# controlo_rev2.net
KiCad netlist of a schematic drawn in Altium Designer
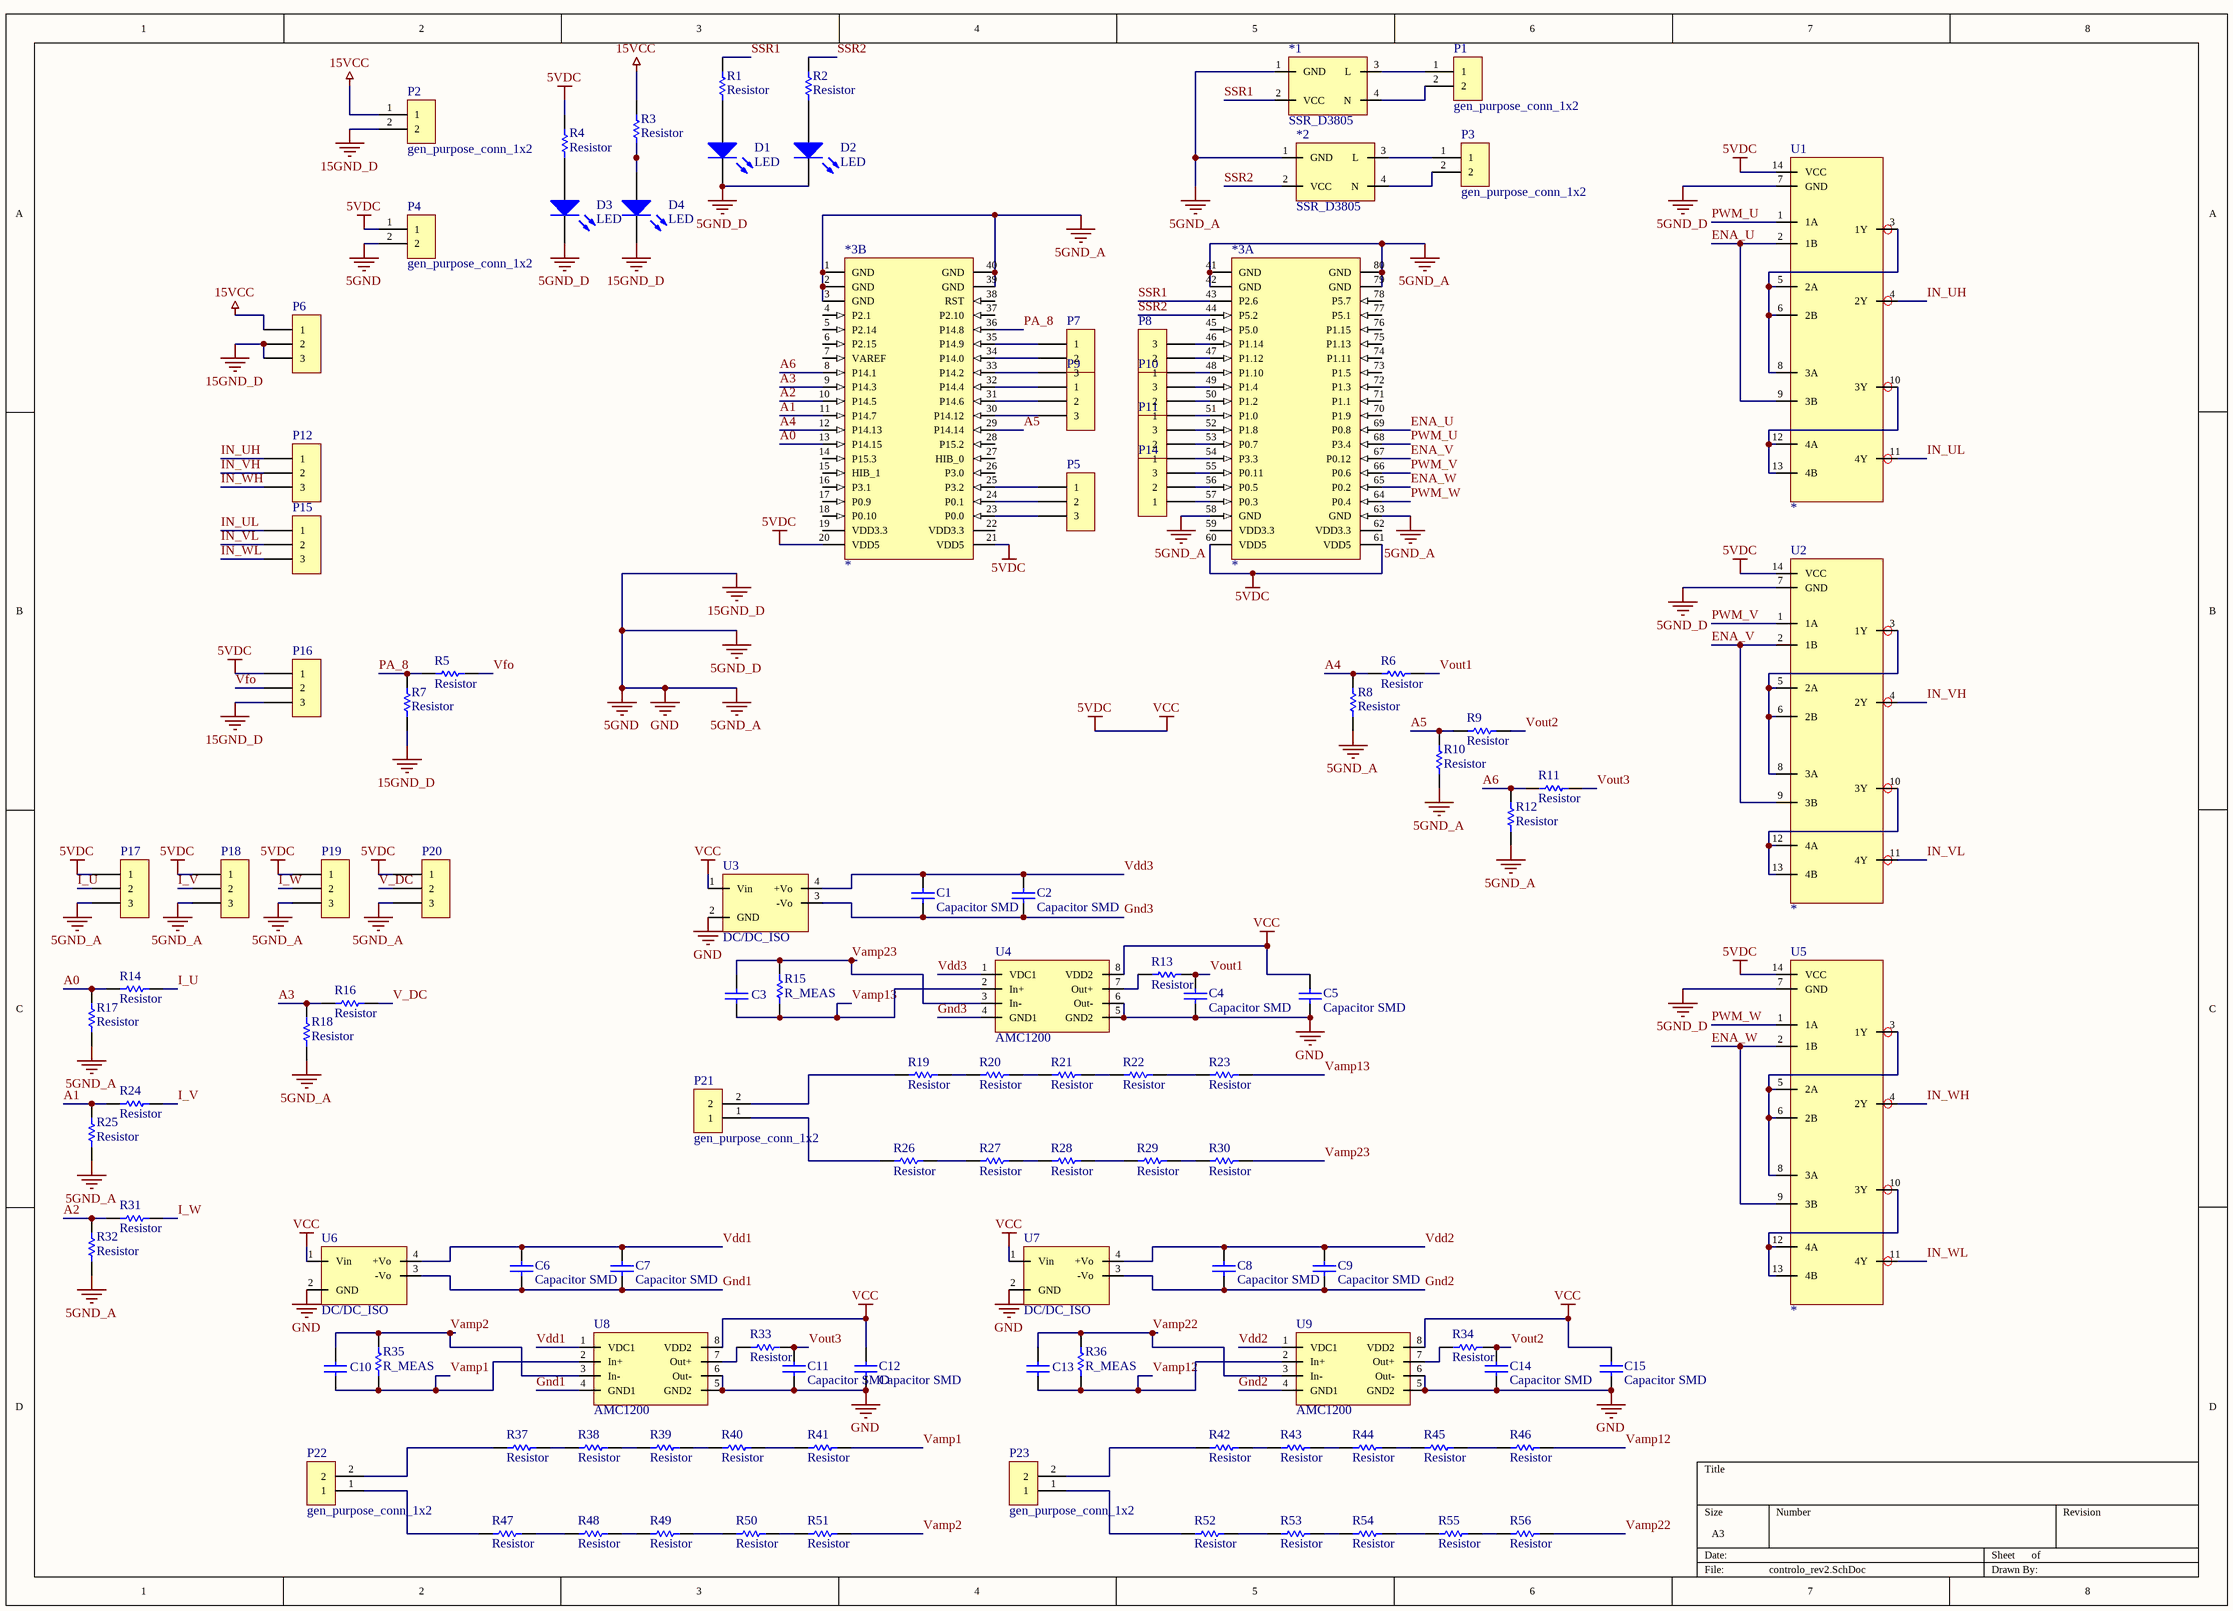
[diagram p0: controlo_rev2.SchDoc]

(export (version "E")
  (design (tool "Eeschema 10.0.6"))
  (components
    (comp (ref "*1")
      (value "SSR_D3805")
      (footprint "SSR_D3805HK")
      (libsource (lib "vmorais_libraries") (part "SSR_D3805"))
    )
    (comp (ref "*2")
      (value "SSR_D3805")
      (footprint "SSR_D3805HK")
      (libsource (lib "vmorais_libraries") (part "SSR_D3805"))
    )
    (comp (ref "*3") (value "*") (footprint "XMC4500") (libsource (lib "vmorais_libraries") (part "XMC4500")))
    (comp (ref "C1")
      (value "Capacitor SMD")
      (footprint "CAPC_0805")
      (description "10uF")
      (libsource (lib "vi_measurement") (part "Capacitor SMD"))
    )
    (comp (ref "C2")
      (value "Capacitor SMD")
      (footprint "CAPC_0805")
      (description "10uF")
      (libsource (lib "vi_measurement") (part "Capacitor SMD"))
    )
    (comp (ref "C3")
      (value "Capacitor SMD")
      (footprint "CAPC_0805")
      (description "1uF")
      (libsource (lib "vi_measurement") (part "Capacitor SMD"))
    )
    (comp (ref "C4")
      (value "Capacitor SMD")
      (footprint "CAPC_0805")
      (description "1uF")
      (libsource (lib "vi_measurement") (part "Capacitor SMD"))
    )
    (comp (ref "C5")
      (value "Capacitor SMD")
      (footprint "CAPC_0805")
      (description "10uF")
      (libsource (lib "vi_measurement") (part "Capacitor SMD"))
    )
    (comp (ref "C6")
      (value "Capacitor SMD")
      (footprint "CAPC_0805")
      (description "10uF")
      (libsource (lib "vi_measurement") (part "Capacitor SMD"))
    )
    (comp (ref "C7")
      (value "Capacitor SMD")
      (footprint "CAPC_0805")
      (description "10uF")
      (libsource (lib "vi_measurement") (part "Capacitor SMD"))
    )
    (comp (ref "C8")
      (value "Capacitor SMD")
      (footprint "CAPC_0805")
      (description "10uF")
      (libsource (lib "vi_measurement") (part "Capacitor SMD"))
    )
    (comp (ref "C9")
      (value "Capacitor SMD")
      (footprint "CAPC_0805")
      (description "10uF")
      (libsource (lib "vi_measurement") (part "Capacitor SMD"))
    )
    (comp (ref "C10")
      (value "Capacitor SMD")
      (footprint "CAPC_0805")
      (description "1uF")
      (libsource (lib "vi_measurement") (part "Capacitor SMD"))
    )
    (comp (ref "C11")
      (value "Capacitor SMD")
      (footprint "CAPC_0805")
      (description "1uF")
      (libsource (lib "vi_measurement") (part "Capacitor SMD"))
    )
    (comp (ref "C12")
      (value "Capacitor SMD")
      (footprint "CAPC_0805")
      (description "10uF")
      (libsource (lib "vi_measurement") (part "Capacitor SMD"))
    )
    (comp (ref "C13")
      (value "Capacitor SMD")
      (footprint "CAPC_0805")
      (description "1uF")
      (libsource (lib "vi_measurement") (part "Capacitor SMD"))
    )
    (comp (ref "C14")
      (value "Capacitor SMD")
      (footprint "CAPC_0805")
      (description "1uF")
      (libsource (lib "vi_measurement") (part "Capacitor SMD"))
    )
    (comp (ref "C15")
      (value "Capacitor SMD")
      (footprint "CAPC_0805")
      (description "10uF")
      (libsource (lib "vi_measurement") (part "Capacitor SMD"))
    )
    (comp (ref "D1")
      (value "LED")
      (footprint "DIODE_1206")
      (libsource (lib "vmorais_libraries") (part "LED"))
    )
    (comp (ref "D2")
      (value "LED")
      (footprint "DIODE_1206")
      (libsource (lib "vmorais_libraries") (part "LED"))
    )
    (comp (ref "D3")
      (value "LED")
      (footprint "DIODE_1206")
      (libsource (lib "vmorais_libraries") (part "LED"))
    )
    (comp (ref "D4")
      (value "LED")
      (footprint "DIODE_1206")
      (libsource (lib "vmorais_libraries") (part "LED"))
    )
    (comp (ref "P1")
      (value "gen_purpose_conn_1x2")
      (footprint "connector1x2_parafuso")
      (libsource (lib "") (part "gen_purpose_conn_1x2_1"))
    )
    (comp (ref "P2")
      (value "gen_purpose_conn_1x2")
      (footprint "connector1x2_parafuso")
      (libsource (lib "") (part "gen_purpose_conn_1x2_1"))
    )
    (comp (ref "P3")
      (value "gen_purpose_conn_1x2")
      (footprint "connector1x2_parafuso")
      (libsource (lib "") (part "gen_purpose_conn_1x2_1"))
    )
    (comp (ref "P4")
      (value "gen_purpose_conn_1x2")
      (footprint "connector1x2_parafuso")
      (libsource (lib "") (part "gen_purpose_conn_1x2_1"))
    )
    (comp (ref "P5")
      (value "Header 3")
      (footprint "HDR1X3_simple")
      (description "Header, 3 pin")
      (libsource (lib "vmorais_libraries") (part "Header 3"))
    )
    (comp (ref "P6")
      (value "Header 3")
      (description "Header, 3 pin")
      (libsource (lib "vmorais_libraries") (part "Header 3"))
    )
    (comp (ref "P7")
      (value "Header 3")
      (footprint "HDR1X3_simple")
      (description "Header, 3 pin")
      (libsource (lib "vmorais_libraries") (part "Header 3"))
    )
    (comp (ref "P8")
      (value "Header 3")
      (footprint "HDR1X3_simple")
      (description "Header, 3 pin")
      (libsource (lib "") (part "Header 3_1"))
    )
    (comp (ref "P9")
      (value "Header 3")
      (footprint "HDR1X3_simple")
      (description "Header, 3 pin")
      (libsource (lib "vmorais_libraries") (part "Header 3"))
    )
    (comp (ref "P10")
      (value "Header 3")
      (footprint "HDR1X3_simple")
      (description "Header, 3 pin")
      (libsource (lib "") (part "Header 3_1"))
    )
    (comp (ref "P11")
      (value "Header 3")
      (footprint "HDR1X3_simple")
      (description "Header, 3 pin")
      (libsource (lib "") (part "Header 3_1"))
    )
    (comp (ref "P12")
      (value "Header 3")
      (description "Header, 3 pin")
      (libsource (lib "vmorais_libraries") (part "Header 3"))
    )
    (comp (ref "P14")
      (value "Header 3")
      (footprint "HDR1X3_simple")
      (description "Header, 3 pin")
      (libsource (lib "") (part "Header 3_1"))
    )
    (comp (ref "P15")
      (value "Header 3")
      (description "Header, 3 pin")
      (libsource (lib "vmorais_libraries") (part "Header 3"))
    )
    (comp (ref "P16")
      (value "Header 3")
      (description "Header, 3 pin")
      (libsource (lib "vmorais_libraries") (part "Header 3"))
    )
    (comp (ref "P17")
      (value "Header 3")
      (description "Header, 3 pin")
      (libsource (lib "vmorais_libraries") (part "Header 3"))
    )
    (comp (ref "P18")
      (value "Header 3")
      (description "Header, 3 pin")
      (libsource (lib "vmorais_libraries") (part "Header 3"))
    )
    (comp (ref "P19")
      (value "Header 3")
      (description "Header, 3 pin")
      (libsource (lib "vmorais_libraries") (part "Header 3"))
    )
    (comp (ref "P20")
      (value "Header 3")
      (description "Header, 3 pin")
      (libsource (lib "vmorais_libraries") (part "Header 3"))
    )
    (comp (ref "P21")
      (value "gen_purpose_conn_1x2")
      (footprint "connector1x2_parafuso")
      (libsource (lib "malvega_pcb") (part "gen_purpose_conn_1x2"))
    )
    (comp (ref "P22")
      (value "gen_purpose_conn_1x2")
      (footprint "connector1x2_parafuso")
      (libsource (lib "malvega_pcb") (part "gen_purpose_conn_1x2"))
    )
    (comp (ref "P23")
      (value "gen_purpose_conn_1x2")
      (footprint "connector1x2_parafuso")
      (libsource (lib "malvega_pcb") (part "gen_purpose_conn_1x2"))
    )
    (comp (ref "R1")
      (value "Resistor")
      (footprint "RESC_0805")
      (libsource (lib "vmorais_libraries") (part "Resistor"))
    )
    (comp (ref "R2")
      (value "Resistor")
      (footprint "RESC_0805")
      (libsource (lib "vmorais_libraries") (part "Resistor"))
    )
    (comp (ref "R3")
      (value "Resistor")
      (footprint "RESC_0805")
      (libsource (lib "vmorais_libraries") (part "Resistor"))
    )
    (comp (ref "R4")
      (value "Resistor")
      (footprint "RESC_0805")
      (libsource (lib "vmorais_libraries") (part "Resistor"))
    )
    (comp (ref "R5")
      (value "Resistor")
      (footprint "RESC_0805")
      (description "5K")
      (libsource (lib "inversor_50a") (part "Resistor"))
    )
    (comp (ref "R6")
      (value "Resistor")
      (footprint "RESC_0805")
      (description "5K")
      (libsource (lib "inversor_50a") (part "Resistor"))
    )
    (comp (ref "R7")
      (value "Resistor")
      (footprint "RESC_0805")
      (description "7K5")
      (libsource (lib "inversor_50a") (part "Resistor"))
    )
    (comp (ref "R8")
      (value "Resistor")
      (footprint "RESC_0805")
      (description "7K5")
      (libsource (lib "inversor_50a") (part "Resistor"))
    )
    (comp (ref "R9")
      (value "Resistor")
      (footprint "RESC_0805")
      (description "5K")
      (libsource (lib "inversor_50a") (part "Resistor"))
    )
    (comp (ref "R10")
      (value "Resistor")
      (footprint "RESC_0805")
      (description "7K5")
      (libsource (lib "inversor_50a") (part "Resistor"))
    )
    (comp (ref "R11")
      (value "Resistor")
      (footprint "RESC_0805")
      (description "5K")
      (libsource (lib "inversor_50a") (part "Resistor"))
    )
    (comp (ref "R12")
      (value "Resistor")
      (footprint "RESC_0805")
      (description "7K5")
      (libsource (lib "inversor_50a") (part "Resistor"))
    )
    (comp (ref "R13")
      (value "Resistor")
      (footprint "RESC_0805")
      (description "330R")
      (libsource (lib "inversor_50a") (part "Resistor"))
    )
    (comp (ref "R14")
      (value "Resistor")
      (footprint "RESC_0805")
      (description "5K")
      (libsource (lib "inversor_50a") (part "Resistor"))
    )
    (comp (ref "R15")
      (value "R_MEAS")
      (footprint "RESC_0805")
      (description "150R")
      (libsource (lib "inversor_50a") (part "Resistor"))
    )
    (comp (ref "R16")
      (value "Resistor")
      (footprint "RESC_0805")
      (description "5K")
      (libsource (lib "inversor_50a") (part "Resistor"))
    )
    (comp (ref "R17")
      (value "Resistor")
      (footprint "RESC_0805")
      (description "7K5")
      (libsource (lib "inversor_50a") (part "Resistor"))
    )
    (comp (ref "R18")
      (value "Resistor")
      (footprint "RESC_0805")
      (description "7K5")
      (libsource (lib "inversor_50a") (part "Resistor"))
    )
    (comp (ref "R19")
      (value "Resistor")
      (footprint "RESC_0805")
      (description "30K")
      (libsource (lib "inversor_50a") (part "Resistor"))
    )
    (comp (ref "R20")
      (value "Resistor")
      (footprint "RESC_0805")
      (description "30K")
      (libsource (lib "inversor_50a") (part "Resistor"))
    )
    (comp (ref "R21")
      (value "Resistor")
      (footprint "RESC_0805")
      (description "30K")
      (libsource (lib "inversor_50a") (part "Resistor"))
    )
    (comp (ref "R22")
      (value "Resistor")
      (footprint "RESC_0805")
      (description "30K")
      (libsource (lib "inversor_50a") (part "Resistor"))
    )
    (comp (ref "R23")
      (value "Resistor")
      (footprint "RESC_0805")
      (description "30K")
      (libsource (lib "inversor_50a") (part "Resistor"))
    )
    (comp (ref "R24")
      (value "Resistor")
      (footprint "RESC_0805")
      (description "5K")
      (libsource (lib "inversor_50a") (part "Resistor"))
    )
    (comp (ref "R25")
      (value "Resistor")
      (footprint "RESC_0805")
      (description "7K5")
      (libsource (lib "inversor_50a") (part "Resistor"))
    )
    (comp (ref "R26")
      (value "Resistor")
      (footprint "RESC_0805")
      (description "30K")
      (libsource (lib "inversor_50a") (part "Resistor"))
    )
    (comp (ref "R27")
      (value "Resistor")
      (footprint "RESC_0805")
      (description "30K")
      (libsource (lib "inversor_50a") (part "Resistor"))
    )
    (comp (ref "R28")
      (value "Resistor")
      (footprint "RESC_0805")
      (description "30K")
      (libsource (lib "inversor_50a") (part "Resistor"))
    )
    (comp (ref "R29")
      (value "Resistor")
      (footprint "RESC_0805")
      (description "30K")
      (libsource (lib "inversor_50a") (part "Resistor"))
    )
    (comp (ref "R30")
      (value "Resistor")
      (footprint "RESC_0805")
      (description "30K")
      (libsource (lib "inversor_50a") (part "Resistor"))
    )
    (comp (ref "R31")
      (value "Resistor")
      (footprint "RESC_0805")
      (description "5K")
      (libsource (lib "inversor_50a") (part "Resistor"))
    )
    (comp (ref "R32")
      (value "Resistor")
      (footprint "RESC_0805")
      (description "7K5")
      (libsource (lib "inversor_50a") (part "Resistor"))
    )
    (comp (ref "R33")
      (value "Resistor")
      (footprint "RESC_0805")
      (description "330R")
      (libsource (lib "inversor_50a") (part "Resistor"))
    )
    (comp (ref "R34")
      (value "Resistor")
      (footprint "RESC_0805")
      (description "330R")
      (libsource (lib "inversor_50a") (part "Resistor"))
    )
    (comp (ref "R35")
      (value "R_MEAS")
      (footprint "RESC_0805")
      (description "150R")
      (libsource (lib "inversor_50a") (part "Resistor"))
    )
    (comp (ref "R36")
      (value "R_MEAS")
      (footprint "RESC_0805")
      (description "150R")
      (libsource (lib "inversor_50a") (part "Resistor"))
    )
    (comp (ref "R37")
      (value "Resistor")
      (footprint "RESC_0805")
      (description "30K")
      (libsource (lib "inversor_50a") (part "Resistor"))
    )
    (comp (ref "R38")
      (value "Resistor")
      (footprint "RESC_0805")
      (description "30K")
      (libsource (lib "inversor_50a") (part "Resistor"))
    )
    (comp (ref "R39")
      (value "Resistor")
      (footprint "RESC_0805")
      (description "30K")
      (libsource (lib "inversor_50a") (part "Resistor"))
    )
    (comp (ref "R40")
      (value "Resistor")
      (footprint "RESC_0805")
      (description "30K")
      (libsource (lib "inversor_50a") (part "Resistor"))
    )
    (comp (ref "R41")
      (value "Resistor")
      (footprint "RESC_0805")
      (description "30K")
      (libsource (lib "inversor_50a") (part "Resistor"))
    )
    (comp (ref "R42")
      (value "Resistor")
      (footprint "RESC_0805")
      (description "30K")
      (libsource (lib "inversor_50a") (part "Resistor"))
    )
    (comp (ref "R43")
      (value "Resistor")
      (footprint "RESC_0805")
      (description "30K")
      (libsource (lib "inversor_50a") (part "Resistor"))
    )
    (comp (ref "R44")
      (value "Resistor")
      (footprint "RESC_0805")
      (description "30K")
      (libsource (lib "inversor_50a") (part "Resistor"))
    )
    (comp (ref "R45")
      (value "Resistor")
      (footprint "RESC_0805")
      (description "30K")
      (libsource (lib "inversor_50a") (part "Resistor"))
    )
    (comp (ref "R46")
      (value "Resistor")
      (footprint "RESC_0805")
      (description "30K")
      (libsource (lib "inversor_50a") (part "Resistor"))
    )
    (comp (ref "R47")
      (value "Resistor")
      (footprint "RESC_0805")
      (description "30K")
      (libsource (lib "inversor_50a") (part "Resistor"))
    )
    (comp (ref "R48")
      (value "Resistor")
      (footprint "RESC_0805")
      (description "30K")
      (libsource (lib "inversor_50a") (part "Resistor"))
    )
    (comp (ref "R49")
      (value "Resistor")
      (footprint "RESC_0805")
      (description "30K")
      (libsource (lib "inversor_50a") (part "Resistor"))
    )
    (comp (ref "R50")
      (value "Resistor")
      (footprint "RESC_0805")
      (description "30K")
      (libsource (lib "inversor_50a") (part "Resistor"))
    )
    (comp (ref "R51")
      (value "Resistor")
      (footprint "RESC_0805")
      (description "30K")
      (libsource (lib "inversor_50a") (part "Resistor"))
    )
    (comp (ref "R52")
      (value "Resistor")
      (footprint "RESC_0805")
      (description "30K")
      (libsource (lib "inversor_50a") (part "Resistor"))
    )
    (comp (ref "R53")
      (value "Resistor")
      (footprint "RESC_0805")
      (description "30K")
      (libsource (lib "inversor_50a") (part "Resistor"))
    )
    (comp (ref "R54")
      (value "Resistor")
      (footprint "RESC_0805")
      (description "30K")
      (libsource (lib "inversor_50a") (part "Resistor"))
    )
    (comp (ref "R55")
      (value "Resistor")
      (footprint "RESC_0805")
      (description "30K")
      (libsource (lib "inversor_50a") (part "Resistor"))
    )
    (comp (ref "R56")
      (value "Resistor")
      (footprint "RESC_0805")
      (description "30K")
      (libsource (lib "inversor_50a") (part "Resistor"))
    )
    (comp (ref "U1")
      (value "*")
      (footprint "SOIC-14N")
      (libsource (lib "vmorais_libraries") (part "HEF4011"))
    )
    (comp (ref "U2")
      (value "*")
      (footprint "SOIC-14N")
      (libsource (lib "vmorais_libraries") (part "HEF4011"))
    )
    (comp (ref "U3")
      (value "DC/DC_ISO")
      (footprint "DC/DC_ISO")
      (libsource (lib "vi_measurement") (part "DC/DC_ISO"))
    )
    (comp (ref "U4")
      (value "AMC1200")
      (footprint "SOIC8")
      (libsource (lib "vi_measurement") (part "AMC1200"))
    )
    (comp (ref "U5")
      (value "*")
      (footprint "SOIC-14N")
      (libsource (lib "vmorais_libraries") (part "HEF4011"))
    )
    (comp (ref "U6")
      (value "DC/DC_ISO")
      (footprint "DC/DC_ISO")
      (libsource (lib "vi_measurement") (part "DC/DC_ISO"))
    )
    (comp (ref "U7")
      (value "DC/DC_ISO")
      (footprint "DC/DC_ISO")
      (libsource (lib "vi_measurement") (part "DC/DC_ISO"))
    )
    (comp (ref "U8")
      (value "AMC1200")
      (footprint "SOIC8")
      (libsource (lib "vi_measurement") (part "AMC1200"))
    )
    (comp (ref "U9")
      (value "AMC1200")
      (footprint "SOIC8")
      (libsource (lib "vi_measurement") (part "AMC1200"))
    )
  )
  (nets
    (net (code "1") (name "/A0") (class "Default")
      (node (ref "*3") (pin "13") (pinfunction "P14.15_13") (pintype "input"))
      (node (ref "R14") (pin "1") (pinfunction "1_1") (pintype "passive"))
      (node (ref "R17") (pin "2") (pinfunction "2_2") (pintype "passive"))
    )
    (net (code "2") (name "/A1") (class "Default")
      (node (ref "*3") (pin "11") (pinfunction "P14.7_11") (pintype "input"))
      (node (ref "R24") (pin "1") (pinfunction "1_1") (pintype "passive"))
      (node (ref "R25") (pin "2") (pinfunction "2_2") (pintype "passive"))
    )
    (net (code "3") (name "/A2") (class "Default")
      (node (ref "*3") (pin "10") (pinfunction "P14.5_10") (pintype "input"))
      (node (ref "R31") (pin "1") (pinfunction "1_1") (pintype "passive"))
      (node (ref "R32") (pin "2") (pinfunction "2_2") (pintype "passive"))
    )
    (net (code "4") (name "/A3") (class "Default")
      (node (ref "*3") (pin "9") (pinfunction "P14.3_9") (pintype "input"))
      (node (ref "R16") (pin "1") (pinfunction "1_1") (pintype "passive"))
      (node (ref "R18") (pin "2") (pinfunction "2_2") (pintype "passive"))
    )
    (net (code "5") (name "/A4") (class "Default")
      (node (ref "*3") (pin "12") (pinfunction "P14.13_12") (pintype "input"))
      (node (ref "R6") (pin "1") (pinfunction "1_1") (pintype "passive"))
      (node (ref "R8") (pin "2") (pinfunction "2_2") (pintype "passive"))
    )
    (net (code "6") (name "/A5") (class "Default")
      (node (ref "*3") (pin "29") (pinfunction "P14.14_29") (pintype "input"))
      (node (ref "R10") (pin "2") (pinfunction "2_2") (pintype "passive"))
      (node (ref "R9") (pin "1") (pinfunction "1_1") (pintype "passive"))
    )
    (net (code "7") (name "/A6") (class "Default")
      (node (ref "*3") (pin "8") (pinfunction "P14.1_8") (pintype "input"))
      (node (ref "R11") (pin "1") (pinfunction "1_1") (pintype "passive"))
      (node (ref "R12") (pin "2") (pinfunction "2_2") (pintype "passive"))
    )
    (net (code "8") (name "/ENA_U") (class "Default")
      (node (ref "*3") (pin "69") (pinfunction "P0.8_69") (pintype "input"))
      (node (ref "U1") (pin "2") (pinfunction "1B_2") (pintype "passive"))
      (node (ref "U1") (pin "9") (pinfunction "3B_9") (pintype "passive"))
    )
    (net (code "9") (name "/ENA_V") (class "Default")
      (node (ref "*3") (pin "67") (pinfunction "P0.12_67") (pintype "input"))
      (node (ref "U2") (pin "2") (pinfunction "1B_2") (pintype "passive"))
      (node (ref "U2") (pin "9") (pinfunction "3B_9") (pintype "passive"))
    )
    (net (code "10") (name "/ENA_W") (class "Default")
      (node (ref "*3") (pin "65") (pinfunction "P0.2_65") (pintype "input"))
      (node (ref "U5") (pin "2") (pinfunction "1B_2") (pintype "passive"))
      (node (ref "U5") (pin "9") (pinfunction "3B_9") (pintype "passive"))
    )
    (net (code "11") (name "/Gnd1") (class "Default")
      (node (ref "C6") (pin "1") (pinfunction "1_1") (pintype "passive"))
      (node (ref "C7") (pin "1") (pinfunction "1_1") (pintype "passive"))
      (node (ref "U6") (pin "3") (pinfunction "-Vo_3") (pintype "passive"))
      (node (ref "U8") (pin "4") (pinfunction "GND1_4") (pintype "passive"))
    )
    (net (code "12") (name "/Gnd2") (class "Default")
      (node (ref "C8") (pin "1") (pinfunction "1_1") (pintype "passive"))
      (node (ref "C9") (pin "1") (pinfunction "1_1") (pintype "passive"))
      (node (ref "U7") (pin "3") (pinfunction "-Vo_3") (pintype "passive"))
      (node (ref "U9") (pin "4") (pinfunction "GND1_4") (pintype "passive"))
    )
    (net (code "13") (name "/Gnd3") (class "Default")
      (node (ref "C1") (pin "1") (pinfunction "1_1") (pintype "passive"))
      (node (ref "C2") (pin "1") (pinfunction "1_1") (pintype "passive"))
      (node (ref "U3") (pin "3") (pinfunction "-Vo_3") (pintype "passive"))
      (node (ref "U4") (pin "4") (pinfunction "GND1_4") (pintype "passive"))
    )
    (net (code "14") (name "/IN_UH") (class "Default")
      (node (ref "P12") (pin "1") (pinfunction "1_1") (pintype "passive"))
      (node (ref "U1") (pin "4") (pinfunction "2Y_4") (pintype "passive"))
    )
    (net (code "15") (name "/IN_UL") (class "Default")
      (node (ref "P15") (pin "1") (pinfunction "1_1") (pintype "passive"))
      (node (ref "U1") (pin "11") (pinfunction "4Y_11") (pintype "passive"))
    )
    (net (code "16") (name "/IN_VH") (class "Default")
      (node (ref "P12") (pin "2") (pinfunction "2_2") (pintype "passive"))
      (node (ref "U2") (pin "4") (pinfunction "2Y_4") (pintype "passive"))
    )
    (net (code "17") (name "/IN_VL") (class "Default")
      (node (ref "P15") (pin "2") (pinfunction "2_2") (pintype "passive"))
      (node (ref "U2") (pin "11") (pinfunction "4Y_11") (pintype "passive"))
    )
    (net (code "18") (name "/IN_WH") (class "Default")
      (node (ref "P12") (pin "3") (pinfunction "3_3") (pintype "passive"))
      (node (ref "U5") (pin "4") (pinfunction "2Y_4") (pintype "passive"))
    )
    (net (code "19") (name "/IN_WL") (class "Default")
      (node (ref "P15") (pin "3") (pinfunction "3_3") (pintype "passive"))
      (node (ref "U5") (pin "11") (pinfunction "4Y_11") (pintype "passive"))
    )
    (net (code "20") (name "/I_U") (class "Default")
      (node (ref "P17") (pin "2") (pinfunction "2_2") (pintype "passive"))
      (node (ref "R14") (pin "2") (pinfunction "2_2") (pintype "passive"))
    )
    (net (code "21") (name "/I_V") (class "Default")
      (node (ref "P18") (pin "2") (pinfunction "2_2") (pintype "passive"))
      (node (ref "R24") (pin "2") (pinfunction "2_2") (pintype "passive"))
    )
    (net (code "22") (name "/I_W") (class "Default")
      (node (ref "P19") (pin "2") (pinfunction "2_2") (pintype "passive"))
      (node (ref "R31") (pin "2") (pinfunction "2_2") (pintype "passive"))
    )
    (net (code "23") (name "/PA_8") (class "Default")
      (node (ref "*3") (pin "36") (pinfunction "P14.8_36") (pintype "input"))
      (node (ref "R5") (pin "1") (pinfunction "1_1") (pintype "passive"))
      (node (ref "R7") (pin "2") (pinfunction "2_2") (pintype "passive"))
    )
    (net (code "24") (name "/PWM_U") (class "Default")
      (node (ref "*3") (pin "68") (pinfunction "P3.4_68") (pintype "input"))
      (node (ref "U1") (pin "1") (pinfunction "1A_1") (pintype "passive"))
    )
    (net (code "25") (name "/PWM_V") (class "Default")
      (node (ref "*3") (pin "66") (pinfunction "P0.6_66") (pintype "input"))
      (node (ref "U2") (pin "1") (pinfunction "1A_1") (pintype "passive"))
    )
    (net (code "26") (name "/PWM_W") (class "Default")
      (node (ref "*3") (pin "64") (pinfunction "P0.4_64") (pintype "input"))
      (node (ref "U5") (pin "1") (pinfunction "1A_1") (pintype "passive"))
    )
    (net (code "27") (name "/SSR1") (class "Default")
      (node (ref "*1") (pin "2") (pinfunction "VCC_2") (pintype "passive"))
      (node (ref "*3") (pin "43") (pinfunction "P2.6_43") (pintype "power_in"))
      (node (ref "R1") (pin "2") (pinfunction "2_2") (pintype "passive"))
    )
    (net (code "28") (name "/SSR2") (class "Default")
      (node (ref "*2") (pin "2") (pinfunction "VCC_2") (pintype "passive"))
      (node (ref "*3") (pin "44") (pinfunction "P5.2_44") (pintype "input"))
      (node (ref "R2") (pin "2") (pinfunction "2_2") (pintype "passive"))
    )
    (net (code "29") (name "/V_DC") (class "Default")
      (node (ref "P20") (pin "2") (pinfunction "2_2") (pintype "passive"))
      (node (ref "R16") (pin "2") (pinfunction "2_2") (pintype "passive"))
    )
    (net (code "30") (name "/Vamp1") (class "Default")
      (node (ref "C10") (pin "1") (pinfunction "1_1") (pintype "passive"))
      (node (ref "R35") (pin "1") (pinfunction "1_1") (pintype "passive"))
      (node (ref "R41") (pin "2") (pinfunction "2_2") (pintype "passive"))
      (node (ref "U8") (pin "2") (pinfunction "In+_2") (pintype "passive"))
    )
    (net (code "31") (name "/Vamp2") (class "Default")
      (node (ref "C10") (pin "2") (pinfunction "2_2") (pintype "passive"))
      (node (ref "R35") (pin "2") (pinfunction "2_2") (pintype "passive"))
      (node (ref "R51") (pin "2") (pinfunction "2_2") (pintype "passive"))
      (node (ref "U8") (pin "3") (pinfunction "In-_3") (pintype "passive"))
    )
    (net (code "32") (name "/Vamp12") (class "Default")
      (node (ref "C13") (pin "1") (pinfunction "1_1") (pintype "passive"))
      (node (ref "R36") (pin "1") (pinfunction "1_1") (pintype "passive"))
      (node (ref "R46") (pin "2") (pinfunction "2_2") (pintype "passive"))
      (node (ref "U9") (pin "2") (pinfunction "In+_2") (pintype "passive"))
    )
    (net (code "33") (name "/Vamp13") (class "Default")
      (node (ref "C3") (pin "1") (pinfunction "1_1") (pintype "passive"))
      (node (ref "R15") (pin "1") (pinfunction "1_1") (pintype "passive"))
      (node (ref "R23") (pin "2") (pinfunction "2_2") (pintype "passive"))
      (node (ref "U4") (pin "2") (pinfunction "In+_2") (pintype "passive"))
    )
    (net (code "34") (name "/Vamp22") (class "Default")
      (node (ref "C13") (pin "2") (pinfunction "2_2") (pintype "passive"))
      (node (ref "R36") (pin "2") (pinfunction "2_2") (pintype "passive"))
      (node (ref "R56") (pin "2") (pinfunction "2_2") (pintype "passive"))
      (node (ref "U9") (pin "3") (pinfunction "In-_3") (pintype "passive"))
    )
    (net (code "35") (name "/Vamp23") (class "Default")
      (node (ref "C3") (pin "2") (pinfunction "2_2") (pintype "passive"))
      (node (ref "R15") (pin "2") (pinfunction "2_2") (pintype "passive"))
      (node (ref "R30") (pin "2") (pinfunction "2_2") (pintype "passive"))
      (node (ref "U4") (pin "3") (pinfunction "In-_3") (pintype "passive"))
    )
    (net (code "36") (name "/Vdd1") (class "Default")
      (node (ref "C6") (pin "2") (pinfunction "2_2") (pintype "passive"))
      (node (ref "C7") (pin "2") (pinfunction "2_2") (pintype "passive"))
      (node (ref "U6") (pin "4") (pinfunction "+Vo_4") (pintype "passive"))
      (node (ref "U8") (pin "1") (pinfunction "VDC1_1") (pintype "passive"))
    )
    (net (code "37") (name "/Vdd2") (class "Default")
      (node (ref "C8") (pin "2") (pinfunction "2_2") (pintype "passive"))
      (node (ref "C9") (pin "2") (pinfunction "2_2") (pintype "passive"))
      (node (ref "U7") (pin "4") (pinfunction "+Vo_4") (pintype "passive"))
      (node (ref "U9") (pin "1") (pinfunction "VDC1_1") (pintype "passive"))
    )
    (net (code "38") (name "/Vdd3") (class "Default")
      (node (ref "C1") (pin "2") (pinfunction "2_2") (pintype "passive"))
      (node (ref "C2") (pin "2") (pinfunction "2_2") (pintype "passive"))
      (node (ref "U3") (pin "4") (pinfunction "+Vo_4") (pintype "passive"))
      (node (ref "U4") (pin "1") (pinfunction "VDC1_1") (pintype "passive"))
    )
    (net (code "39") (name "/Vfo") (class "Default")
      (node (ref "P16") (pin "2") (pinfunction "2_2") (pintype "passive"))
      (node (ref "R5") (pin "2") (pinfunction "2_2") (pintype "passive"))
    )
    (net (code "40") (name "/Vout1") (class "Default")
      (node (ref "C4") (pin "2") (pinfunction "2_2") (pintype "passive"))
      (node (ref "R13") (pin "2") (pinfunction "2_2") (pintype "passive"))
      (node (ref "R6") (pin "2") (pinfunction "2_2") (pintype "passive"))
    )
    (net (code "41") (name "/Vout2") (class "Default")
      (node (ref "C14") (pin "2") (pinfunction "2_2") (pintype "passive"))
      (node (ref "R34") (pin "2") (pinfunction "2_2") (pintype "passive"))
      (node (ref "R9") (pin "2") (pinfunction "2_2") (pintype "passive"))
    )
    (net (code "42") (name "/Vout3") (class "Default")
      (node (ref "C11") (pin "2") (pinfunction "2_2") (pintype "passive"))
      (node (ref "R11") (pin "2") (pinfunction "2_2") (pintype "passive"))
      (node (ref "R33") (pin "2") (pinfunction "2_2") (pintype "passive"))
    )
    (net (code "43") (name "5VDC") (class "Default")
      (node (ref "*3") (pin "20") (pinfunction "VDD5_20") (pintype "power_in"))
      (node (ref "*3") (pin "21") (pinfunction "VDD5_21") (pintype "power_in"))
      (node (ref "*3") (pin "60") (pinfunction "VDD5_60") (pintype "power_in"))
      (node (ref "*3") (pin "61") (pinfunction "VDD5_61") (pintype "power_in"))
      (node (ref "C12") (pin "2") (pinfunction "2_2") (pintype "passive"))
      (node (ref "C15") (pin "2") (pinfunction "2_2") (pintype "passive"))
      (node (ref "C5") (pin "2") (pinfunction "2_2") (pintype "passive"))
      (node (ref "P16") (pin "1") (pinfunction "1_1") (pintype "passive"))
      (node (ref "P17") (pin "1") (pinfunction "1_1") (pintype "passive"))
      (node (ref "P18") (pin "1") (pinfunction "1_1") (pintype "passive"))
      (node (ref "P19") (pin "1") (pinfunction "1_1") (pintype "passive"))
      (node (ref "P20") (pin "1") (pinfunction "1_1") (pintype "passive"))
      (node (ref "P4") (pin "1") (pinfunction "1_1") (pintype "passive"))
      (node (ref "R4") (pin "2") (pinfunction "2_2") (pintype "passive"))
      (node (ref "U1") (pin "14") (pinfunction "VCC_14") (pintype "passive"))
      (node (ref "U2") (pin "14") (pinfunction "VCC_14") (pintype "passive"))
      (node (ref "U3") (pin "1") (pinfunction "Vin_1") (pintype "passive"))
      (node (ref "U4") (pin "8") (pinfunction "VDD2_8") (pintype "passive"))
      (node (ref "U5") (pin "14") (pinfunction "VCC_14") (pintype "passive"))
      (node (ref "U6") (pin "1") (pinfunction "Vin_1") (pintype "passive"))
      (node (ref "U7") (pin "1") (pinfunction "Vin_1") (pintype "passive"))
      (node (ref "U8") (pin "8") (pinfunction "VDD2_8") (pintype "passive"))
      (node (ref "U9") (pin "8") (pinfunction "VDD2_8") (pintype "passive"))
    )
    (net (code "44") (name "15GND_D") (class "Default")
      (node (ref "*1") (pin "1") (pinfunction "GND_1") (pintype "passive"))
      (node (ref "*2") (pin "1") (pinfunction "GND_1") (pintype "passive"))
      (node (ref "*3") (pin "1") (pinfunction "GND_1") (pintype "power_in"))
      (node (ref "*3") (pin "2") (pinfunction "GND_2") (pintype "power_in"))
      (node (ref "*3") (pin "3") (pinfunction "GND_3") (pintype "power_in"))
      (node (ref "*3") (pin "39") (pinfunction "GND_39") (pintype "power_in"))
      (node (ref "*3") (pin "40") (pinfunction "GND_40") (pintype "power_in"))
      (node (ref "*3") (pin "41") (pinfunction "GND_41") (pintype "power_in"))
      (node (ref "*3") (pin "42") (pinfunction "GND_42") (pintype "power_in"))
      (node (ref "*3") (pin "58") (pinfunction "GND_58") (pintype "input"))
      (node (ref "*3") (pin "63") (pinfunction "GND_63") (pintype "input"))
      (node (ref "*3") (pin "79") (pinfunction "GND_79") (pintype "power_in"))
      (node (ref "*3") (pin "80") (pinfunction "GND_80") (pintype "power_in"))
      (node (ref "C11") (pin "1") (pinfunction "1_1") (pintype "passive"))
      (node (ref "C12") (pin "1") (pinfunction "1_1") (pintype "passive"))
      (node (ref "C14") (pin "1") (pinfunction "1_1") (pintype "passive"))
      (node (ref "C15") (pin "1") (pinfunction "1_1") (pintype "passive"))
      (node (ref "C4") (pin "1") (pinfunction "1_1") (pintype "passive"))
      (node (ref "C5") (pin "1") (pinfunction "1_1") (pintype "passive"))
      (node (ref "D1") (pin "2") (pinfunction "K_2") (pintype "passive"))
      (node (ref "D2") (pin "2") (pinfunction "K_2") (pintype "passive"))
      (node (ref "D3") (pin "2") (pinfunction "K_2") (pintype "passive"))
      (node (ref "D4") (pin "2") (pinfunction "K_2") (pintype "passive"))
      (node (ref "P16") (pin "3") (pinfunction "3_3") (pintype "passive"))
      (node (ref "P17") (pin "3") (pinfunction "3_3") (pintype "passive"))
      (node (ref "P18") (pin "3") (pinfunction "3_3") (pintype "passive"))
      (node (ref "P19") (pin "3") (pinfunction "3_3") (pintype "passive"))
      (node (ref "P2") (pin "2") (pinfunction "2_2") (pintype "passive"))
      (node (ref "P20") (pin "3") (pinfunction "3_3") (pintype "passive"))
      (node (ref "P4") (pin "2") (pinfunction "2_2") (pintype "passive"))
      (node (ref "P6") (pin "2") (pinfunction "2_2") (pintype "passive"))
      (node (ref "P6") (pin "3") (pinfunction "3_3") (pintype "passive"))
      (node (ref "R10") (pin "1") (pinfunction "1_1") (pintype "passive"))
      (node (ref "R12") (pin "1") (pinfunction "1_1") (pintype "passive"))
      (node (ref "R17") (pin "1") (pinfunction "1_1") (pintype "passive"))
      (node (ref "R18") (pin "1") (pinfunction "1_1") (pintype "passive"))
      (node (ref "R25") (pin "1") (pinfunction "1_1") (pintype "passive"))
      (node (ref "R32") (pin "1") (pinfunction "1_1") (pintype "passive"))
      (node (ref "R7") (pin "1") (pinfunction "1_1") (pintype "passive"))
      (node (ref "R8") (pin "1") (pinfunction "1_1") (pintype "passive"))
      (node (ref "U1") (pin "7") (pinfunction "GND_7") (pintype "passive"))
      (node (ref "U2") (pin "7") (pinfunction "GND_7") (pintype "passive"))
      (node (ref "U3") (pin "2") (pinfunction "GND_2") (pintype "passive"))
      (node (ref "U4") (pin "5") (pinfunction "GND2_5") (pintype "passive"))
      (node (ref "U4") (pin "6") (pinfunction "Out-_6") (pintype "passive"))
      (node (ref "U5") (pin "7") (pinfunction "GND_7") (pintype "passive"))
      (node (ref "U6") (pin "2") (pinfunction "GND_2") (pintype "passive"))
      (node (ref "U7") (pin "2") (pinfunction "GND_2") (pintype "passive"))
      (node (ref "U8") (pin "5") (pinfunction "GND2_5") (pintype "passive"))
      (node (ref "U8") (pin "6") (pinfunction "Out-_6") (pintype "passive"))
      (node (ref "U9") (pin "5") (pinfunction "GND2_5") (pintype "passive"))
      (node (ref "U9") (pin "6") (pinfunction "Out-_6") (pintype "passive"))
    )
    (net (code "45") (name "15VCC") (class "Default")
      (node (ref "P2") (pin "1") (pinfunction "1_1") (pintype "passive"))
      (node (ref "P6") (pin "1") (pinfunction "1_1") (pintype "passive"))
      (node (ref "R3") (pin "2") (pinfunction "2_2") (pintype "passive"))
    )
    (net (code "46") (name "Net-(*1-L)") (class "Default")
      (node (ref "*1") (pin "3") (pinfunction "L_3") (pintype "passive"))
      (node (ref "P1") (pin "1") (pinfunction "1_1") (pintype "passive"))
    )
    (net (code "47") (name "Net-(*1-N)") (class "Default")
      (node (ref "*1") (pin "4") (pinfunction "N_4") (pintype "passive"))
      (node (ref "P1") (pin "2") (pinfunction "2_2") (pintype "passive"))
    )
    (net (code "48") (name "Net-(*2-L)") (class "Default")
      (node (ref "*2") (pin "3") (pinfunction "L_3") (pintype "passive"))
      (node (ref "P3") (pin "1") (pinfunction "1_1") (pintype "passive"))
    )
    (net (code "49") (name "Net-(*2-N)") (class "Default")
      (node (ref "*2") (pin "4") (pinfunction "N_4") (pintype "passive"))
      (node (ref "P3") (pin "2") (pinfunction "2_2") (pintype "passive"))
    )
    (net (code "50") (name "Net-(*3A-P0.3)") (class "Default")
      (node (ref "*3") (pin "57") (pinfunction "P0.3_57") (pintype "input"))
      (node (ref "P14") (pin "1") (pinfunction "1_1") (pintype "passive"))
    )
    (net (code "51") (name "Net-(*3A-P0.5)") (class "Default")
      (node (ref "*3") (pin "56") (pinfunction "P0.5_56") (pintype "input"))
      (node (ref "P14") (pin "2") (pinfunction "2_2") (pintype "passive"))
    )
    (net (code "52") (name "Net-(*3A-P0.7)") (class "Default")
      (node (ref "*3") (pin "53") (pinfunction "P0.7_53") (pintype "input"))
      (node (ref "P11") (pin "2") (pinfunction "2_2") (pintype "passive"))
    )
    (net (code "53") (name "Net-(*3A-P0.11)") (class "Default")
      (node (ref "*3") (pin "55") (pinfunction "P0.11_55") (pintype "input"))
      (node (ref "P14") (pin "3") (pinfunction "3_3") (pintype "passive"))
    )
    (net (code "54") (name "Net-(*3A-P1.0)") (class "Default")
      (node (ref "*3") (pin "51") (pinfunction "P1.0_51") (pintype "input"))
      (node (ref "P10") (pin "1") (pinfunction "1_1") (pintype "passive"))
    )
    (net (code "55") (name "Net-(*3A-P1.2)") (class "Default")
      (node (ref "*3") (pin "50") (pinfunction "P1.2_50") (pintype "input"))
      (node (ref "P10") (pin "2") (pinfunction "2_2") (pintype "passive"))
    )
    (net (code "56") (name "Net-(*3A-P1.4)") (class "Default")
      (node (ref "*3") (pin "49") (pinfunction "P1.4_49") (pintype "input"))
      (node (ref "P10") (pin "3") (pinfunction "3_3") (pintype "passive"))
    )
    (net (code "57") (name "Net-(*3A-P1.8)") (class "Default")
      (node (ref "*3") (pin "52") (pinfunction "P1.8_52") (pintype "input"))
      (node (ref "P11") (pin "3") (pinfunction "3_3") (pintype "passive"))
    )
    (net (code "58") (name "Net-(*3A-P1.10)") (class "Default")
      (node (ref "*3") (pin "48") (pinfunction "P1.10_48") (pintype "input"))
      (node (ref "P8") (pin "1") (pinfunction "1_1") (pintype "passive"))
    )
    (net (code "59") (name "Net-(*3A-P1.12)") (class "Default")
      (node (ref "*3") (pin "47") (pinfunction "P1.12_47") (pintype "input"))
      (node (ref "P8") (pin "2") (pinfunction "2_2") (pintype "passive"))
    )
    (net (code "60") (name "Net-(*3A-P1.14)") (class "Default")
      (node (ref "*3") (pin "46") (pinfunction "P1.14_46") (pintype "input"))
      (node (ref "P8") (pin "3") (pinfunction "3_3") (pintype "passive"))
    )
    (net (code "61") (name "Net-(*3A-P3.3)") (class "Default")
      (node (ref "*3") (pin "54") (pinfunction "P3.3_54") (pintype "input"))
      (node (ref "P11") (pin "1") (pinfunction "1_1") (pintype "passive"))
    )
    (net (code "62") (name "Net-(*3B-P0.0)") (class "Default")
      (node (ref "*3") (pin "23") (pinfunction "P0.0_23") (pintype "input"))
      (node (ref "P5") (pin "3") (pinfunction "3_3") (pintype "passive"))
    )
    (net (code "63") (name "Net-(*3B-P0.1)") (class "Default")
      (node (ref "*3") (pin "24") (pinfunction "P0.1_24") (pintype "input"))
      (node (ref "P5") (pin "2") (pinfunction "2_2") (pintype "passive"))
    )
    (net (code "64") (name "Net-(*3B-P3.2)") (class "Default")
      (node (ref "*3") (pin "25") (pinfunction "P3.2_25") (pintype "input"))
      (node (ref "P5") (pin "1") (pinfunction "1_1") (pintype "passive"))
    )
    (net (code "65") (name "Net-(*3B-P14.0)") (class "Default")
      (node (ref "*3") (pin "34") (pinfunction "P14.0_34") (pintype "input"))
      (node (ref "P7") (pin "2") (pinfunction "2_2") (pintype "passive"))
    )
    (net (code "66") (name "Net-(*3B-P14.2)") (class "Default")
      (node (ref "*3") (pin "33") (pinfunction "P14.2_33") (pintype "input"))
      (node (ref "P7") (pin "3") (pinfunction "3_3") (pintype "passive"))
    )
    (net (code "67") (name "Net-(*3B-P14.4)") (class "Default")
      (node (ref "*3") (pin "32") (pinfunction "P14.4_32") (pintype "input"))
      (node (ref "P9") (pin "1") (pinfunction "1_1") (pintype "passive"))
    )
    (net (code "68") (name "Net-(*3B-P14.6)") (class "Default")
      (node (ref "*3") (pin "31") (pinfunction "P14.6_31") (pintype "input"))
      (node (ref "P9") (pin "2") (pinfunction "2_2") (pintype "passive"))
    )
    (net (code "69") (name "Net-(*3B-P14.9)") (class "Default")
      (node (ref "*3") (pin "35") (pinfunction "P14.9_35") (pintype "input"))
      (node (ref "P7") (pin "1") (pinfunction "1_1") (pintype "passive"))
    )
    (net (code "70") (name "Net-(*3B-P14.12)") (class "Default")
      (node (ref "*3") (pin "30") (pinfunction "P14.12_30") (pintype "input"))
      (node (ref "P9") (pin "3") (pinfunction "3_3") (pintype "passive"))
    )
    (net (code "71") (name "Net-(D1-A)") (class "Default")
      (node (ref "D1") (pin "1") (pinfunction "A_1") (pintype "passive"))
      (node (ref "R1") (pin "1") (pinfunction "1_1") (pintype "passive"))
    )
    (net (code "72") (name "Net-(D2-A)") (class "Default")
      (node (ref "D2") (pin "1") (pinfunction "A_1") (pintype "passive"))
      (node (ref "R2") (pin "1") (pinfunction "1_1") (pintype "passive"))
    )
    (net (code "73") (name "Net-(D3-A)") (class "Default")
      (node (ref "D3") (pin "1") (pinfunction "A_1") (pintype "passive"))
      (node (ref "R4") (pin "1") (pinfunction "1_1") (pintype "passive"))
    )
    (net (code "74") (name "Net-(D4-A)") (class "Default")
      (node (ref "D4") (pin "1") (pinfunction "A_1") (pintype "passive"))
      (node (ref "R3") (pin "1") (pinfunction "1_1") (pintype "passive"))
    )
    (net (code "75") (name "Net-(P21-Pad1)") (class "Default")
      (node (ref "P21") (pin "1") (pinfunction "1_1") (pintype "passive"))
      (node (ref "R26") (pin "1") (pinfunction "1_1") (pintype "passive"))
    )
    (net (code "76") (name "Net-(P21-Pad2)") (class "Default")
      (node (ref "P21") (pin "2") (pinfunction "2_2") (pintype "passive"))
      (node (ref "R19") (pin "1") (pinfunction "1_1") (pintype "passive"))
    )
    (net (code "77") (name "Net-(P22-Pad1)") (class "Default")
      (node (ref "P22") (pin "1") (pinfunction "1_1") (pintype "passive"))
      (node (ref "R47") (pin "1") (pinfunction "1_1") (pintype "passive"))
    )
    (net (code "78") (name "Net-(P22-Pad2)") (class "Default")
      (node (ref "P22") (pin "2") (pinfunction "2_2") (pintype "passive"))
      (node (ref "R37") (pin "1") (pinfunction "1_1") (pintype "passive"))
    )
    (net (code "79") (name "Net-(P23-Pad1)") (class "Default")
      (node (ref "P23") (pin "1") (pinfunction "1_1") (pintype "passive"))
      (node (ref "R52") (pin "1") (pinfunction "1_1") (pintype "passive"))
    )
    (net (code "80") (name "Net-(P23-Pad2)") (class "Default")
      (node (ref "P23") (pin "2") (pinfunction "2_2") (pintype "passive"))
      (node (ref "R42") (pin "1") (pinfunction "1_1") (pintype "passive"))
    )
    (net (code "81") (name "Net-(R19-Pad2)") (class "Default")
      (node (ref "R19") (pin "2") (pinfunction "2_2") (pintype "passive"))
      (node (ref "R20") (pin "1") (pinfunction "1_1") (pintype "passive"))
    )
    (net (code "82") (name "Net-(R20-Pad2)") (class "Default")
      (node (ref "R20") (pin "2") (pinfunction "2_2") (pintype "passive"))
      (node (ref "R21") (pin "1") (pinfunction "1_1") (pintype "passive"))
    )
    (net (code "83") (name "Net-(R21-Pad2)") (class "Default")
      (node (ref "R21") (pin "2") (pinfunction "2_2") (pintype "passive"))
      (node (ref "R22") (pin "1") (pinfunction "1_1") (pintype "passive"))
    )
    (net (code "84") (name "Net-(R22-Pad2)") (class "Default")
      (node (ref "R22") (pin "2") (pinfunction "2_2") (pintype "passive"))
      (node (ref "R23") (pin "1") (pinfunction "1_1") (pintype "passive"))
    )
    (net (code "85") (name "Net-(R26-Pad2)") (class "Default")
      (node (ref "R26") (pin "2") (pinfunction "2_2") (pintype "passive"))
      (node (ref "R27") (pin "1") (pinfunction "1_1") (pintype "passive"))
    )
    (net (code "86") (name "Net-(R27-Pad2)") (class "Default")
      (node (ref "R27") (pin "2") (pinfunction "2_2") (pintype "passive"))
      (node (ref "R28") (pin "1") (pinfunction "1_1") (pintype "passive"))
    )
    (net (code "87") (name "Net-(R28-Pad2)") (class "Default")
      (node (ref "R28") (pin "2") (pinfunction "2_2") (pintype "passive"))
      (node (ref "R29") (pin "1") (pinfunction "1_1") (pintype "passive"))
    )
    (net (code "88") (name "Net-(R29-Pad2)") (class "Default")
      (node (ref "R29") (pin "2") (pinfunction "2_2") (pintype "passive"))
      (node (ref "R30") (pin "1") (pinfunction "1_1") (pintype "passive"))
    )
    (net (code "89") (name "Net-(R37-Pad2)") (class "Default")
      (node (ref "R37") (pin "2") (pinfunction "2_2") (pintype "passive"))
      (node (ref "R38") (pin "1") (pinfunction "1_1") (pintype "passive"))
    )
    (net (code "90") (name "Net-(R38-Pad2)") (class "Default")
      (node (ref "R38") (pin "2") (pinfunction "2_2") (pintype "passive"))
      (node (ref "R39") (pin "1") (pinfunction "1_1") (pintype "passive"))
    )
    (net (code "91") (name "Net-(R39-Pad2)") (class "Default")
      (node (ref "R39") (pin "2") (pinfunction "2_2") (pintype "passive"))
      (node (ref "R40") (pin "1") (pinfunction "1_1") (pintype "passive"))
    )
    (net (code "92") (name "Net-(R40-Pad2)") (class "Default")
      (node (ref "R40") (pin "2") (pinfunction "2_2") (pintype "passive"))
      (node (ref "R41") (pin "1") (pinfunction "1_1") (pintype "passive"))
    )
    (net (code "93") (name "Net-(R42-Pad2)") (class "Default")
      (node (ref "R42") (pin "2") (pinfunction "2_2") (pintype "passive"))
      (node (ref "R43") (pin "1") (pinfunction "1_1") (pintype "passive"))
    )
    (net (code "94") (name "Net-(R43-Pad2)") (class "Default")
      (node (ref "R43") (pin "2") (pinfunction "2_2") (pintype "passive"))
      (node (ref "R44") (pin "1") (pinfunction "1_1") (pintype "passive"))
    )
    (net (code "95") (name "Net-(R44-Pad2)") (class "Default")
      (node (ref "R44") (pin "2") (pinfunction "2_2") (pintype "passive"))
      (node (ref "R45") (pin "1") (pinfunction "1_1") (pintype "passive"))
    )
    (net (code "96") (name "Net-(R45-Pad2)") (class "Default")
      (node (ref "R45") (pin "2") (pinfunction "2_2") (pintype "passive"))
      (node (ref "R46") (pin "1") (pinfunction "1_1") (pintype "passive"))
    )
    (net (code "97") (name "Net-(R47-Pad2)") (class "Default")
      (node (ref "R47") (pin "2") (pinfunction "2_2") (pintype "passive"))
      (node (ref "R48") (pin "1") (pinfunction "1_1") (pintype "passive"))
    )
    (net (code "98") (name "Net-(R48-Pad2)") (class "Default")
      (node (ref "R48") (pin "2") (pinfunction "2_2") (pintype "passive"))
      (node (ref "R49") (pin "1") (pinfunction "1_1") (pintype "passive"))
    )
    (net (code "99") (name "Net-(R49-Pad2)") (class "Default")
      (node (ref "R49") (pin "2") (pinfunction "2_2") (pintype "passive"))
      (node (ref "R50") (pin "1") (pinfunction "1_1") (pintype "passive"))
    )
    (net (code "100") (name "Net-(R50-Pad2)") (class "Default")
      (node (ref "R50") (pin "2") (pinfunction "2_2") (pintype "passive"))
      (node (ref "R51") (pin "1") (pinfunction "1_1") (pintype "passive"))
    )
    (net (code "101") (name "Net-(R52-Pad2)") (class "Default")
      (node (ref "R52") (pin "2") (pinfunction "2_2") (pintype "passive"))
      (node (ref "R53") (pin "1") (pinfunction "1_1") (pintype "passive"))
    )
    (net (code "102") (name "Net-(R53-Pad2)") (class "Default")
      (node (ref "R53") (pin "2") (pinfunction "2_2") (pintype "passive"))
      (node (ref "R54") (pin "1") (pinfunction "1_1") (pintype "passive"))
    )
    (net (code "103") (name "Net-(R54-Pad2)") (class "Default")
      (node (ref "R54") (pin "2") (pinfunction "2_2") (pintype "passive"))
      (node (ref "R55") (pin "1") (pinfunction "1_1") (pintype "passive"))
    )
    (net (code "104") (name "Net-(R55-Pad2)") (class "Default")
      (node (ref "R55") (pin "2") (pinfunction "2_2") (pintype "passive"))
      (node (ref "R56") (pin "1") (pinfunction "1_1") (pintype "passive"))
    )
    (net (code "105") (name "Net-(U1-1Y)") (class "Default")
      (node (ref "U1") (pin "3") (pinfunction "1Y_3") (pintype "passive"))
      (node (ref "U1") (pin "5") (pinfunction "2A_5") (pintype "passive"))
      (node (ref "U1") (pin "6") (pinfunction "2B_6") (pintype "passive"))
      (node (ref "U1") (pin "8") (pinfunction "3A_8") (pintype "passive"))
    )
    (net (code "106") (name "Net-(U1-3Y)") (class "Default")
      (node (ref "U1") (pin "10") (pinfunction "3Y_10") (pintype "passive"))
      (node (ref "U1") (pin "12") (pinfunction "4A_12") (pintype "passive"))
      (node (ref "U1") (pin "13") (pinfunction "4B_13") (pintype "passive"))
    )
    (net (code "107") (name "Net-(U2-1Y)") (class "Default")
      (node (ref "U2") (pin "3") (pinfunction "1Y_3") (pintype "passive"))
      (node (ref "U2") (pin "5") (pinfunction "2A_5") (pintype "passive"))
      (node (ref "U2") (pin "6") (pinfunction "2B_6") (pintype "passive"))
      (node (ref "U2") (pin "8") (pinfunction "3A_8") (pintype "passive"))
    )
    (net (code "108") (name "Net-(U2-3Y)") (class "Default")
      (node (ref "U2") (pin "10") (pinfunction "3Y_10") (pintype "passive"))
      (node (ref "U2") (pin "12") (pinfunction "4A_12") (pintype "passive"))
      (node (ref "U2") (pin "13") (pinfunction "4B_13") (pintype "passive"))
    )
    (net (code "109") (name "Net-(U4-Out+)") (class "Default")
      (node (ref "R13") (pin "1") (pinfunction "1_1") (pintype "passive"))
      (node (ref "U4") (pin "7") (pinfunction "Out+_7") (pintype "passive"))
    )
    (net (code "110") (name "Net-(U5-1Y)") (class "Default")
      (node (ref "U5") (pin "3") (pinfunction "1Y_3") (pintype "passive"))
      (node (ref "U5") (pin "5") (pinfunction "2A_5") (pintype "passive"))
      (node (ref "U5") (pin "6") (pinfunction "2B_6") (pintype "passive"))
      (node (ref "U5") (pin "8") (pinfunction "3A_8") (pintype "passive"))
    )
    (net (code "111") (name "Net-(U5-3Y)") (class "Default")
      (node (ref "U5") (pin "10") (pinfunction "3Y_10") (pintype "passive"))
      (node (ref "U5") (pin "12") (pinfunction "4A_12") (pintype "passive"))
      (node (ref "U5") (pin "13") (pinfunction "4B_13") (pintype "passive"))
    )
    (net (code "112") (name "Net-(U8-Out+)") (class "Default")
      (node (ref "R33") (pin "1") (pinfunction "1_1") (pintype "passive"))
      (node (ref "U8") (pin "7") (pinfunction "Out+_7") (pintype "passive"))
    )
    (net (code "113") (name "Net-(U9-Out+)") (class "Default")
      (node (ref "R34") (pin "1") (pinfunction "1_1") (pintype "passive"))
      (node (ref "U9") (pin "7") (pinfunction "Out+_7") (pintype "passive"))
    )
    (net (code "114") (name "unconnected-(*3A-P1.1-Pad71)") (class "Default")
      (node (ref "*3") (pin "71") (pinfunction "P1.1_71") (pintype "input"))
    )
    (net (code "115") (name "unconnected-(*3A-P1.3-Pad72)") (class "Default")
      (node (ref "*3") (pin "72") (pinfunction "P1.3_72") (pintype "input"))
    )
    (net (code "116") (name "unconnected-(*3A-P1.5-Pad73)") (class "Default")
      (node (ref "*3") (pin "73") (pinfunction "P1.5_73") (pintype "input"))
    )
    (net (code "117") (name "unconnected-(*3A-P1.9-Pad70)") (class "Default")
      (node (ref "*3") (pin "70") (pinfunction "P1.9_70") (pintype "input"))
    )
    (net (code "118") (name "unconnected-(*3A-P1.11-Pad74)") (class "Default")
      (node (ref "*3") (pin "74") (pinfunction "P1.11_74") (pintype "input"))
    )
    (net (code "119") (name "unconnected-(*3A-P1.13-Pad75)") (class "Default")
      (node (ref "*3") (pin "75") (pinfunction "P1.13_75") (pintype "input"))
    )
    (net (code "120") (name "unconnected-(*3A-P1.15-Pad76)") (class "Default")
      (node (ref "*3") (pin "76") (pinfunction "P1.15_76") (pintype "input"))
    )
    (net (code "121") (name "unconnected-(*3A-P5.0-Pad45)") (class "Default")
      (node (ref "*3") (pin "45") (pinfunction "P5.0_45") (pintype "input"))
    )
    (net (code "122") (name "unconnected-(*3A-P5.1-Pad77)") (class "Default")
      (node (ref "*3") (pin "77") (pinfunction "P5.1_77") (pintype "input"))
    )
    (net (code "123") (name "unconnected-(*3A-P5.7-Pad78)") (class "Default")
      (node (ref "*3") (pin "78") (pinfunction "P5.7_78") (pintype "input"))
    )
    (net (code "124") (name "unconnected-(*3A-VDD3.3-Pad59)") (class "Default")
      (node (ref "*3") (pin "59") (pinfunction "VDD3.3_59") (pintype "power_in"))
    )
    (net (code "125") (name "unconnected-(*3A-VDD3.3-Pad62)") (class "Default")
      (node (ref "*3") (pin "62") (pinfunction "VDD3.3_62") (pintype "power_in"))
    )
    (net (code "126") (name "unconnected-(*3B-HIB_0-Pad27)") (class "Default")
      (node (ref "*3") (pin "27") (pinfunction "HIB_0_27") (pintype "input"))
    )
    (net (code "127") (name "unconnected-(*3B-HIB_1-Pad15)") (class "Default")
      (node (ref "*3") (pin "15") (pinfunction "HIB_1_15") (pintype "input"))
    )
    (net (code "128") (name "unconnected-(*3B-P0.9-Pad17)") (class "Default")
      (node (ref "*3") (pin "17") (pinfunction "P0.9_17") (pintype "input"))
    )
    (net (code "129") (name "unconnected-(*3B-P0.10-Pad18)") (class "Default")
      (node (ref "*3") (pin "18") (pinfunction "P0.10_18") (pintype "input"))
    )
    (net (code "130") (name "unconnected-(*3B-P2.1-Pad4)") (class "Default")
      (node (ref "*3") (pin "4") (pinfunction "P2.1_4") (pintype "input"))
    )
    (net (code "131") (name "unconnected-(*3B-P2.10-Pad37)") (class "Default")
      (node (ref "*3") (pin "37") (pinfunction "P2.10_37") (pintype "input"))
    )
    (net (code "132") (name "unconnected-(*3B-P2.14-Pad5)") (class "Default")
      (node (ref "*3") (pin "5") (pinfunction "P2.14_5") (pintype "input"))
    )
    (net (code "133") (name "unconnected-(*3B-P2.15-Pad6)") (class "Default")
      (node (ref "*3") (pin "6") (pinfunction "P2.15_6") (pintype "input"))
    )
    (net (code "134") (name "unconnected-(*3B-P3.0-Pad26)") (class "Default")
      (node (ref "*3") (pin "26") (pinfunction "P3.0_26") (pintype "input"))
    )
    (net (code "135") (name "unconnected-(*3B-P3.1-Pad16)") (class "Default")
      (node (ref "*3") (pin "16") (pinfunction "P3.1_16") (pintype "input"))
    )
    (net (code "136") (name "unconnected-(*3B-P15.2-Pad28)") (class "Default")
      (node (ref "*3") (pin "28") (pinfunction "P15.2_28") (pintype "input"))
    )
    (net (code "137") (name "unconnected-(*3B-P15.3-Pad14)") (class "Default")
      (node (ref "*3") (pin "14") (pinfunction "P15.3_14") (pintype "input"))
    )
    (net (code "138") (name "unconnected-(*3B-RST-Pad38)") (class "Default")
      (node (ref "*3") (pin "38") (pinfunction "RST_38") (pintype "input"))
    )
    (net (code "139") (name "unconnected-(*3B-VAREF-Pad7)") (class "Default")
      (node (ref "*3") (pin "7") (pinfunction "VAREF_7") (pintype "input"))
    )
    (net (code "140") (name "unconnected-(*3B-VDD3.3-Pad19)") (class "Default")
      (node (ref "*3") (pin "19") (pinfunction "VDD3.3_19") (pintype "power_in"))
    )
    (net (code "141") (name "unconnected-(*3B-VDD3.3-Pad22)") (class "Default")
      (node (ref "*3") (pin "22") (pinfunction "VDD3.3_22") (pintype "power_in"))
    )
  )
)
